# CFS210017030ZZP2005A0.net
KiCad netlist of a schematic drawn in Altium Designer
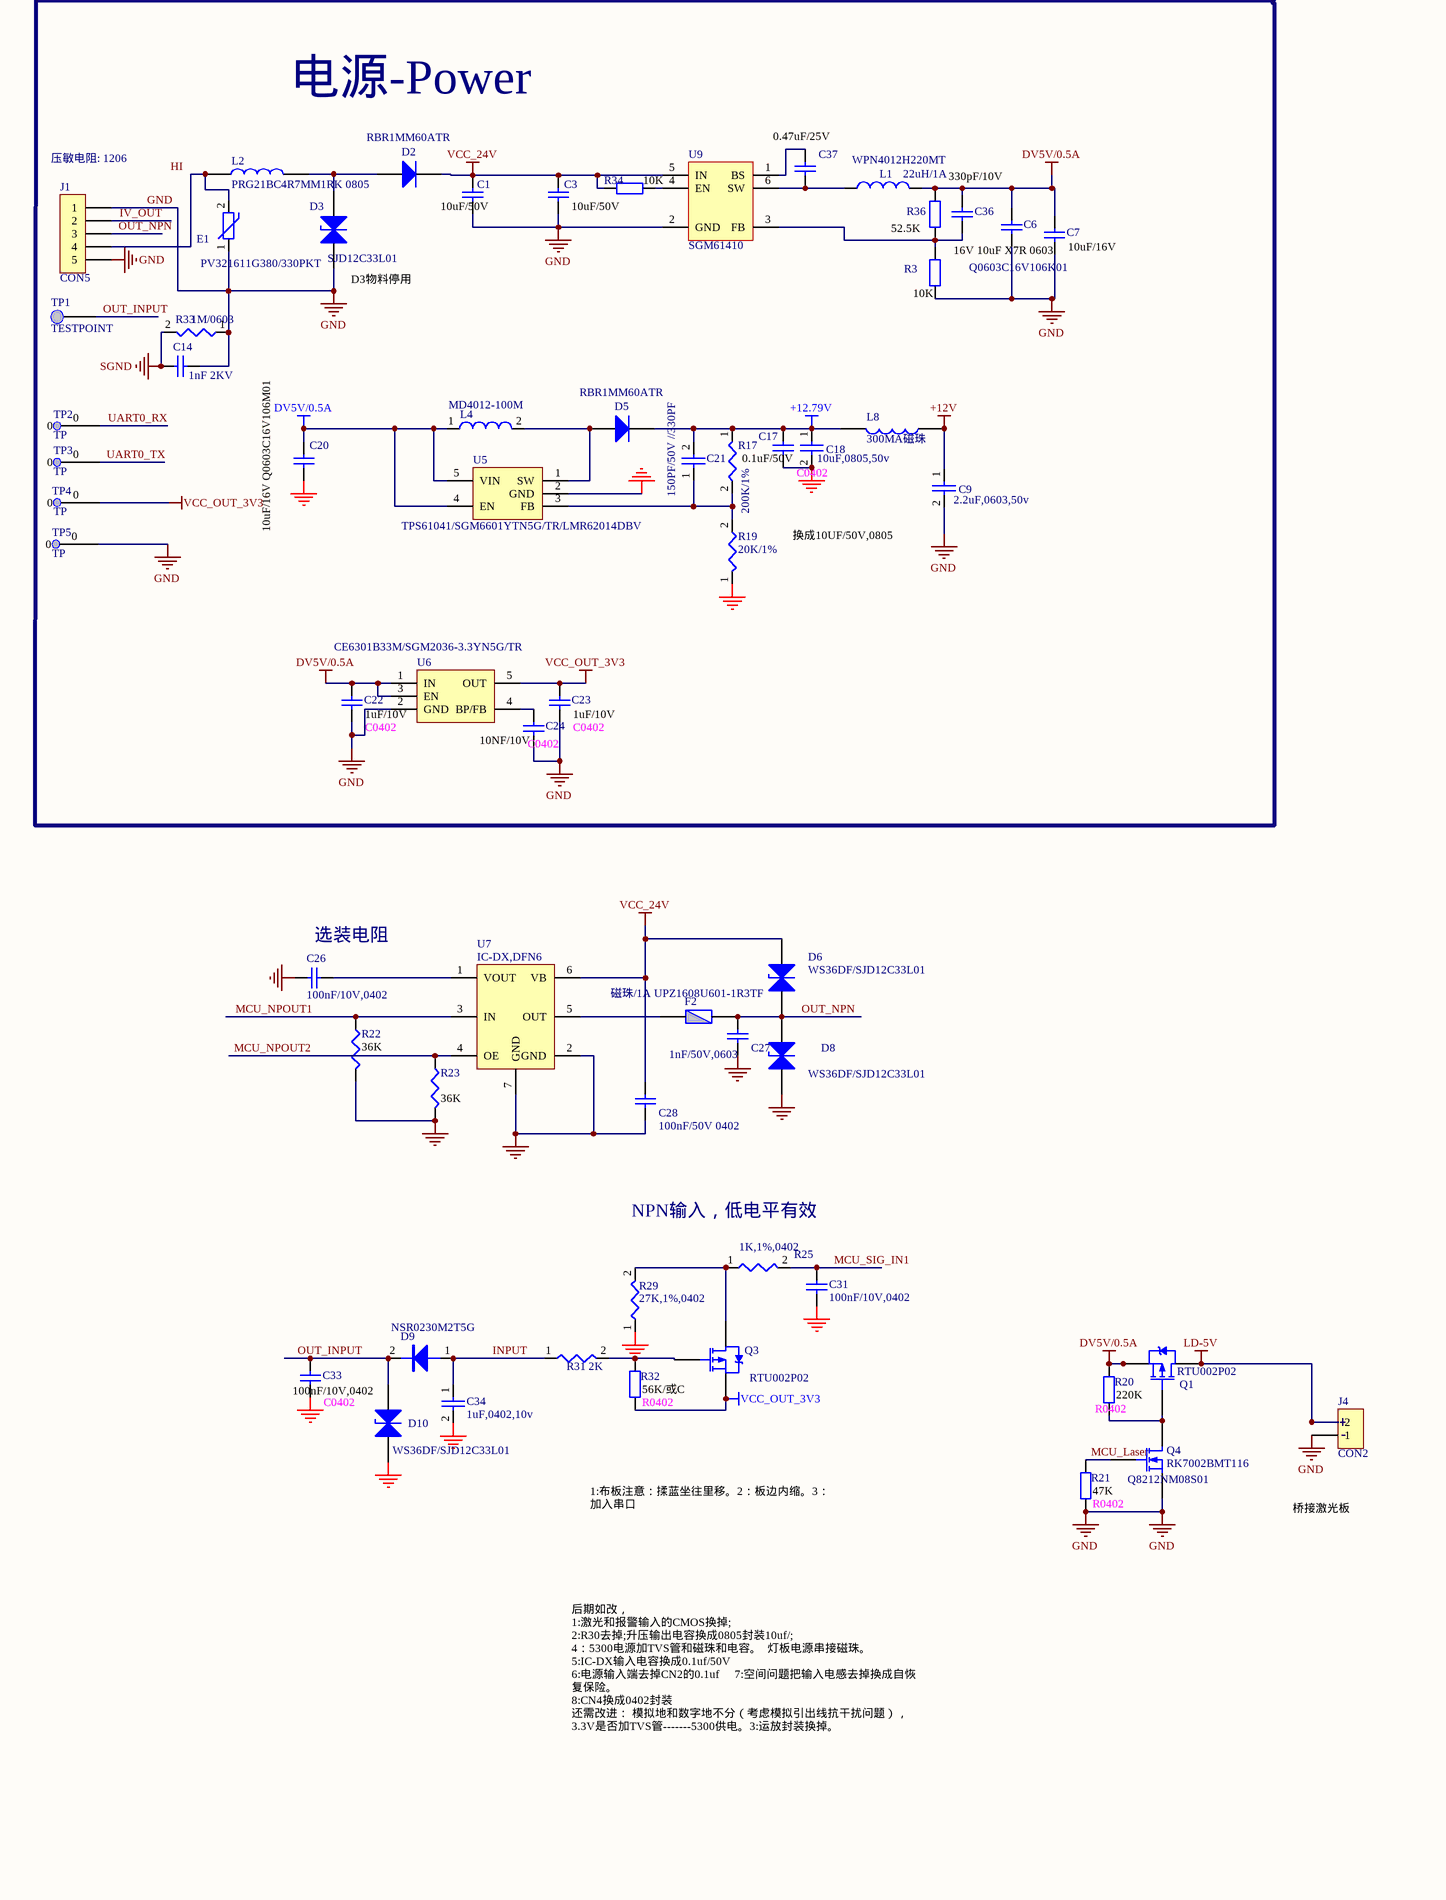
[diagram p0: CFS210017030ZZP2005A0.SchDoc, left]
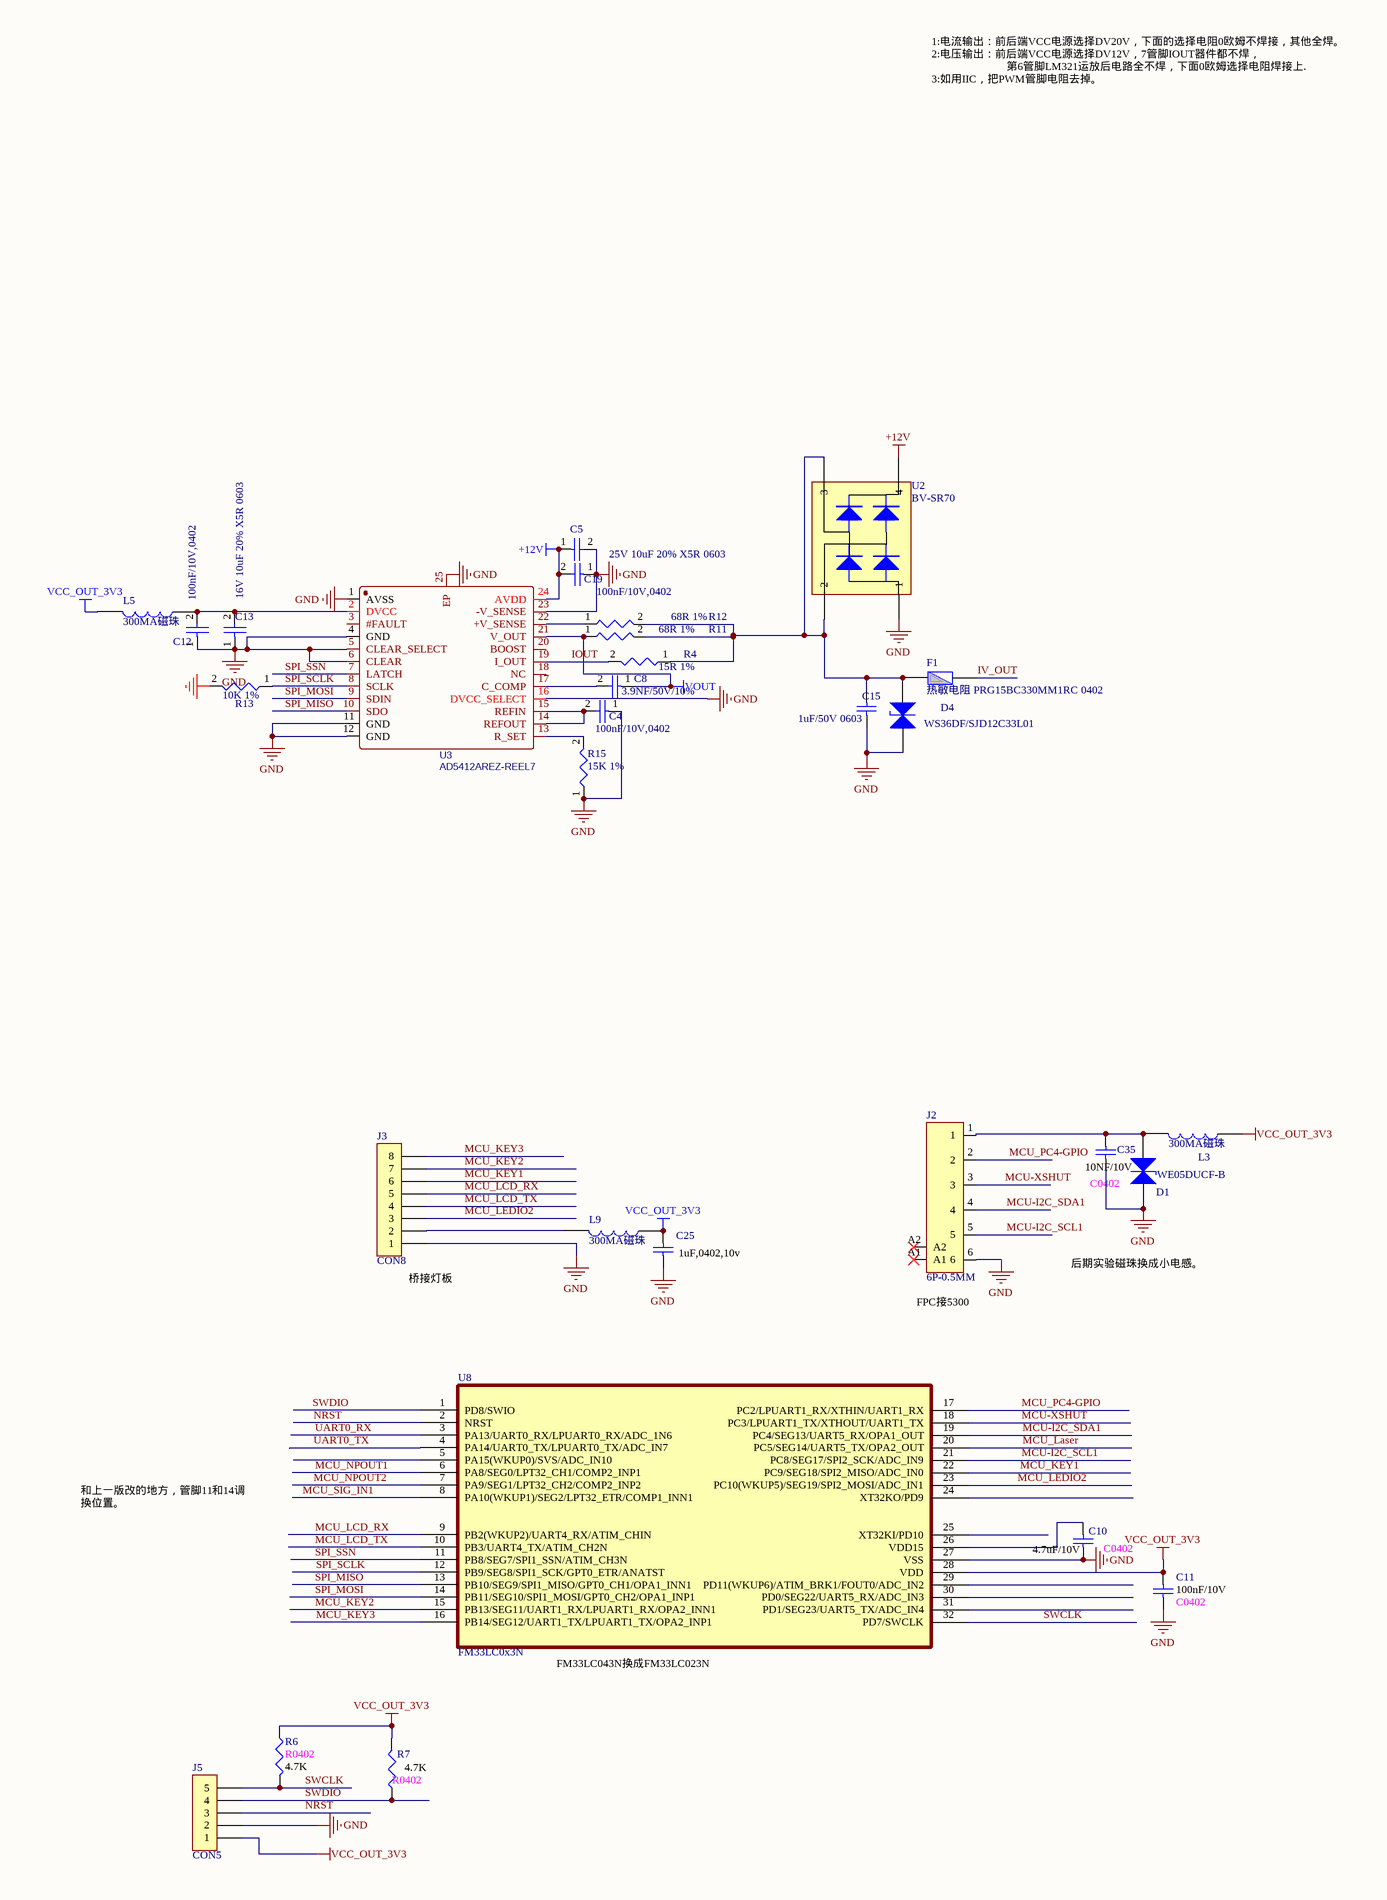
[diagram p1: CFS210017030ZZP2005A0.SchDoc, right]

(export (version "E")
  (design (tool "Eeschema 10.0.6"))
  (components
    (comp (ref "C1")
      (value "10uF/50V")
      (footprint "R0805-Z")
      (description "Capacitor")
      (fields (field (name "Comment") "Q0402C50V223K01") (field (name "PUBLISHER") "Altium Limited"))
      (libsource (lib "Miscellaneous Devices") (part "Cap"))
    )
    (comp (ref "C3")
      (value "10uF/50V")
      (footprint "R0805-Z")
      (description "Capacitor")
      (fields (field (name "Comment") "Q0402C50V223K01") (field (name "PUBLISHER") "Altium Limited"))
      (libsource (lib "Miscellaneous Devices") (part "Cap"))
    )
    (comp (ref "C4")
      (value "100nF/10V,0402")
      (footprint "R0402-Z")
      (description "Capacitor")
      (libsource (lib "*") (part "CAP"))
    )
    (comp (ref "C5")
      (value "25V 10uF 20% X5R 0603")
      (footprint "R0603-Z")
      (description "Capacitor")
      (libsource (lib "*") (part "CAP"))
    )
    (comp (ref "C6")
      (value "Q0603C16V106K01")
      (footprint "R0603-Z")
      (description "Capacitor")
      (fields (field (name "ALTIUM_VALUE") "16V 10uF X7R 0603") (field (name "PUBLISHER") "Altium Limited"))
      (libsource (lib "Miscellaneous Devices") (part "Cap"))
    )
    (comp (ref "C7")
      (value "10uF/16V")
      (footprint "R0603-Z")
      (description "Capacitor")
      (fields (field (name "Comment") "Q0603C16V106K01") (field (name "PUBLISHER") "Altium Limited"))
      (libsource (lib "Miscellaneous Devices") (part "Cap"))
    )
    (comp (ref "C8")
      (value "3.9NF/50V/10%")
      (footprint "R0402-Z")
      (description "Capacitor")
      (libsource (lib "*") (part "CAP"))
    )
    (comp (ref "C9")
      (value "2.2uF,0603,50v")
      (footprint "R0603-Z")
      (description "Capacitor")
      (libsource (lib "*") (part "CAP"))
    )
    (comp (ref "C10")
      (value "4.7uF/10V")
      (footprint "R0402-Z")
      (description "Capacitor (Semiconductor SIM Model)")
      (fields (field (name "PACKAGEREFERENCE") "C0402") (field (name "PUBLISHER") "Altium Limited"))
      (libsource (lib "Miscellaneous Devices") (part "Cap Semi"))
    )
    (comp (ref "C11")
      (value "100nF/10V")
      (footprint "R0402-Z")
      (description "Capacitor (Semiconductor SIM Model)")
      (fields
        (field (name "PACKAGEREFERENCE") "C0402")
        (field (name "Comment") "100nF/10V,0402")
        (field (name "PUBLISHER") "Altium Limited")
      )
      (libsource (lib "Miscellaneous Devices") (part "Cap Semi"))
    )
    (comp (ref "C12")
      (value "100nF/10V,0402")
      (footprint "R0402-Z")
      (description "Capacitor")
      (libsource (lib "*") (part "CAP"))
    )
    (comp (ref "C13")
      (value "16V 10uF 20% X5R 0603")
      (footprint "R0603-Z")
      (description "Capacitor")
      (libsource (lib "*") (part "CAP"))
    )
    (comp (ref "C14")
      (value "1nF 2KV")
      (footprint "CR3216-1206")
      (description "Capacitor")
      (fields (field (name "PUBLISHER") "Altium Limited"))
      (libsource (lib "Miscellaneous Devices") (part "Cap"))
    )
    (comp (ref "C15")
      (value "1uF/50V 0603")
      (footprint "R0603-Z")
      (fields (field (name "PUBLISHER") "Altium Limited"))
      (libsource (lib "Miscellaneous Devices") (part "Cap"))
    )
    (comp (ref "C17")
      (value "0.1uF/50V")
      (footprint "R0402-Z")
      (description "Capacitor")
      (fields
        (field (name "PACKAGEREFERENCE") "C0402")
        (field (name "Comment") "Q0402C50V223K01")
        (field (name "PUBLISHER") "Altium Limited")
      )
      (libsource (lib "Miscellaneous Devices") (part "Cap"))
    )
    (comp (ref "C18")
      (value "10uF,0805,50v")
      (footprint "R0805-Z")
      (description "Capacitor")
      (libsource (lib "*") (part "CAP"))
    )
    (comp (ref "C19")
      (value "100nF/10V,0402")
      (footprint "R0402-Z")
      (description "Capacitor")
      (libsource (lib "*") (part "CAP"))
    )
    (comp (ref "C20")
      (value "10uF/16V Q0603C16V106M01")
      (footprint "R0603-Z")
      (description "Capacitor")
      (fields (field (name "Comment") "Q0603C16V106K01") (field (name "PUBLISHER") "Altium Limited"))
      (libsource (lib "Miscellaneous Devices") (part "Cap"))
    )
    (comp (ref "C21")
      (value "150PF/50V //330PF")
      (footprint "R0402-Z")
      (description "Capacitor")
      (libsource (lib "*") (part "CAP"))
    )
    (comp (ref "C22")
      (value "1uF/10V")
      (footprint "R0402-Z")
      (description "Capacitor")
      (fields
        (field (name "PACKAGEREFERENCE") "C0402")
        (field (name "Comment") "Q0402C50V223K01")
        (field (name "PUBLISHER") "Altium Limited")
      )
      (libsource (lib "Miscellaneous Devices") (part "Cap"))
    )
    (comp (ref "C23")
      (value "1uF/10V")
      (footprint "R0402-Z")
      (description "Capacitor")
      (fields
        (field (name "PACKAGEREFERENCE") "C0402")
        (field (name "Comment") "Q0402C50V223K01")
        (field (name "PUBLISHER") "Altium Limited")
      )
      (libsource (lib "Miscellaneous Devices") (part "Cap"))
    )
    (comp (ref "C24")
      (value "10NF/10V")
      (footprint "R0402-Z")
      (description "Capacitor")
      (fields
        (field (name "PACKAGEREFERENCE") "C0402")
        (field (name "Comment") "Q0402C50V223K01")
        (field (name "PUBLISHER") "Altium Limited")
      )
      (libsource (lib "Miscellaneous Devices") (part "Cap"))
    )
    (comp (ref "C25")
      (value "1uF,0402,10v")
      (footprint "R0402-Z")
      (description "Capacitor (Semiconductor SIM Model)")
      (fields (field (name "PUBLISHER") "Altium Limited"))
      (libsource (lib "Miscellaneous Devices") (part "Cap Semi"))
    )
    (comp (ref "C26")
      (value "100nF/10V,0402")
      (footprint "R0402-Z")
      (description "Capacitor")
      (fields (field (name "PUBLISHER") "Altium Limited"))
      (libsource (lib "*") (part "Cap"))
    )
    (comp (ref "C27")
      (value "1nF/50V,0603")
      (footprint "R0603-Z")
      (description "Capacitor")
      (fields (field (name "PUBLISHER") "Altium Limited"))
      (libsource (lib "*") (part "Cap"))
    )
    (comp (ref "C28")
      (value "100nF/50V 0402")
      (footprint "R0402-Z")
      (description "Capacitor")
      (fields (field (name "PUBLISHER") "Altium Limited"))
      (libsource (lib "*") (part "Cap"))
    )
    (comp (ref "C31")
      (value "100nF/10V,0402")
      (footprint "R0402-Z")
      (description "Capacitor")
      (fields (field (name "PUBLISHER") "Altium Limited"))
      (libsource (lib "*") (part "Cap"))
    )
    (comp (ref "C33")
      (value "100nF/10V,0402")
      (footprint "R0402-Z")
      (description "Capacitor")
      (fields
        (field (name "PACKAGEREFERENCE") "C0402")
        (field (name "Comment") "Q0402C50V223K01")
        (field (name "PUBLISHER") "Altium Limited")
      )
      (libsource (lib "Miscellaneous Devices") (part "Cap"))
    )
    (comp (ref "C34")
      (value "1uF,0402,10v")
      (footprint "R0402-Z")
      (description "Capacitor")
      (libsource (lib "*") (part "CAP"))
    )
    (comp (ref "C35")
      (value "10NF/10V")
      (footprint "R0402-Z")
      (description "Capacitor")
      (fields
        (field (name "PACKAGEREFERENCE") "C0402")
        (field (name "Comment") "Q0402C50V223K01")
        (field (name "PUBLISHER") "Altium Limited")
      )
      (libsource (lib "Miscellaneous Devices") (part "Cap"))
    )
    (comp (ref "C36")
      (value "330pF/10V")
      (footprint "R0402-Z")
      (description "Capacitor")
      (fields (field (name "Comment") "Q0402C50V223K01") (field (name "PUBLISHER") "Altium Limited"))
      (libsource (lib "Miscellaneous Devices") (part "Cap"))
    )
    (comp (ref "C37")
      (value "0.47uF/25V")
      (footprint "R0402-Z")
      (description "Capacitor")
      (fields (field (name "Comment") "Q0402C50V223K01") (field (name "PUBLISHER") "Altium Limited"))
      (libsource (lib "Miscellaneous Devices") (part "Cap"))
    )
    (comp (ref "D1") (value "WE05DUCF-B") (footprint "WS36DF") (libsource (lib "*") (part "PSD36C")))
    (comp (ref "D2")
      (value "RBR1MM60ATR")
      (footprint "SOD-123Z")
      (description "Default Diode")
      (fields (field (name "PUBLISHER") "Altium Limited"))
      (libsource (lib "Miscellaneous Devices") (part "Diode"))
    )
    (comp (ref "D3") (value "SJD12C33L01") (footprint "SOD-123S") (libsource (lib "*") (part "PSD36C")))
    (comp (ref "D4") (value "WS36DF/SJD12C33L01") (footprint "WS36DF") (libsource (lib "*") (part "PSD36C")))
    (comp (ref "D5")
      (value "RBR1MM60ATR")
      (footprint "SOD-123Z")
      (description "Default Diode")
      (fields (field (name "PUBLISHER") "Altium Limited"))
      (libsource (lib "Miscellaneous Devices") (part "Diode"))
    )
    (comp (ref "D6") (value "WS36DF/SJD12C33L01") (footprint "WS36DF") (libsource (lib "*") (part "PSD36C")))
    (comp (ref "D8") (value "WS36DF/SJD12C33L01") (footprint "WS36DF") (libsource (lib "*") (part "PSD36C")))
    (comp (ref "D9")
      (value "NSR0230M2T5G")
      (footprint "SOD723")
      (description "Diode")
      (libsource (lib "*") (part "DIODE"))
    )
    (comp (ref "D10") (value "WS36DF/SJD12C33L01") (footprint "WS36DF") (libsource (lib "*") (part "PSD36C")))
    (comp (ref "E1")
      (value "PV321611G380/330PKT")
      (footprint "FPV3216")
      (description "PV321611G380PKT")
      (fields (field (name "压敏电阻") "1206"))
      (libsource (lib "*") (part "VARISTOR"))
    )
    (comp (ref "F1")
      (value "热敏电阻 PRG15BC330MM1RC 0402")
      (footprint "R0402-Z")
      (description "自恢复保险")
      (libsource (lib "YAANSch20090511") (part "PTC"))
    )
    (comp (ref "F2")
      (value "磁珠/1A UPZ1608U601-1R3TF")
      (footprint "R0603-Z")
      (description "自恢复保险")
      (libsource (lib "YAANSch20090511") (part "PTC"))
    )
    (comp (ref "J1")
      (value "CON5")
      (footprint "CON1.695-5")
      (description "Connector")
      (libsource (lib "YAANSch2021") (part "CON5"))
    )
    (comp (ref "J2") (value "6P-0.5MM") (footprint "FPC-0.5-6") (libsource (lib "*") (part "6PIN_1")))
    (comp (ref "J3")
      (value "CON8")
      (footprint "CON8-QIAOJIE")
      (description "Connector")
      (fields (field (name "MANUFACTURER") "津达电子"))
      (libsource (lib "YAANSch") (part "CON8"))
    )
    (comp (ref "J4")
      (value "CON2")
      (footprint "JIGUANGQIAO")
      (description "Connector")
      (libsource (lib "YAANSch2021") (part "CON2"))
    )
    (comp (ref "J5")
      (value "CON5")
      (footprint "PH1.27-5")
      (description "Connector")
      (fields (field (name "MANUFACTURER") "津达电子"))
      (libsource (lib "YAANSch") (part "CON5"))
    )
    (comp (ref "L1")
      (value "WPN4012H220MT")
      (footprint "WPN4012H220MT")
      (description "Inductor")
      (fields (field (name "ALTIUM_VALUE") "22uH/1A") (field (name "PUBLISHER") "Altium Limited"))
      (libsource (lib "Miscellaneous Devices") (part "Inductor"))
    )
    (comp (ref "L2")
      (value "PRG21BC4R7MM1RK 0805")
      (footprint "R0805-Z")
      (libsource (lib "YAANSch20090511") (part "INDUCTOR1"))
    )
    (comp (ref "L3")
      (value "300MA磁珠")
      (footprint "R0402-Z")
      (libsource (lib "YAANSch20090511") (part "INDUCTOR1"))
    )
    (comp (ref "L4")
      (value "10UH或12UH/1..3A以上")
      (footprint "MD4012-100M")
      (fields (field (name "ALTIUM_UNNAMED_1") "MD4012-100M"))
      (libsource (lib "*") (part "INDUCTOR"))
    )
    (comp (ref "L5")
      (value "300MA磁珠")
      (footprint "R0402-Z")
      (libsource (lib "YAANSch20090511") (part "INDUCTOR1"))
    )
    (comp (ref "L8")
      (value "300MA磁珠")
      (footprint "R0402-Z")
      (libsource (lib "YAANSch20090511") (part "INDUCTOR1"))
    )
    (comp (ref "L9")
      (value "300MA磁珠")
      (footprint "R0402-Z")
      (libsource (lib "YAANSch20090511") (part "INDUCTOR1"))
    )
    (comp (ref "Q1")
      (value "RTU002P02")
      (footprint "SOT-323")
      (description "P-Channel Power MOSFET")
      (fields (field (name "PUBLISHER") "Altium Limited"))
      (libsource (lib "Miscellaneous Devices") (part "PMOS-2"))
    )
    (comp (ref "Q3")
      (value "RTU002P02")
      (footprint "SOT-323")
      (description "P-Channel Power MOSFET")
      (fields (field (name "PUBLISHER") "Altium Limited"))
      (libsource (lib "Miscellaneous Devices") (part "PMOS-2"))
    )
    (comp (ref "Q4")
      (value "RK7002BMT116")
      (footprint "SOT-23")
      (description "N-Channel MOSFET")
      (fields (field (name "ALTIUM_UNNAMED_1") "Q8212NM08S01") (field (name "PUBLISHER") "Altium Limited"))
      (libsource (lib "Miscellaneous Devices") (part "MOSFET-N"))
    )
    (comp (ref "R3")
      (value "10K")
      (footprint "R0402-Z")
      (description "Resistor")
      (fields (field (name "PUBLISHER") "Altium Limited"))
      (libsource (lib "") (part "Res2_1"))
    )
    (comp (ref "R4") (value "15R 1%") (footprint "R0402-Z") (libsource (lib "*") (part "RES1")))
    (comp (ref "R6")
      (value "4.7K")
      (footprint "R0402-Z")
      (description "Resistor")
      (fields (field (name "PACKAGEREFERENCE") "R0402") (field (name "PUBLISHER") "Altium Limited"))
      (libsource (lib "Miscellaneous Devices") (part "Res3"))
    )
    (comp (ref "R7")
      (value "4.7K")
      (footprint "R0402-Z")
      (description "Resistor")
      (fields (field (name "PACKAGEREFERENCE") "R0402") (field (name "PUBLISHER") "Altium Limited"))
      (libsource (lib "Miscellaneous Devices") (part "Res3"))
    )
    (comp (ref "R11") (value "68R 1%") (footprint "R0402-Z") (libsource (lib "*") (part "RES1")))
    (comp (ref "R12") (value "68R 1%") (footprint "R0402-Z") (libsource (lib "*") (part "RES1")))
    (comp (ref "R13") (value "10K 1%") (footprint "R0402-Z") (libsource (lib "*") (part "RES1")))
    (comp (ref "R15") (value "15K 1%") (footprint "R0402-Z") (libsource (lib "*") (part "RES1")))
    (comp (ref "R17") (value "200K/1%") (footprint "R0402-Z") (libsource (lib "*") (part "RES1")))
    (comp (ref "R19") (value "20K/1%") (footprint "R0402-Z") (libsource (lib "*") (part "RES1")))
    (comp (ref "R20")
      (value "220K")
      (footprint "R0402-Z")
      (description "Resistor")
      (fields (field (name "PACKAGEREFERENCE") "R0402") (field (name "PUBLISHER") "Altium Limited"))
      (libsource (lib "") (part "Res2_1"))
    )
    (comp (ref "R21")
      (value "47K")
      (footprint "R0402-Z")
      (description "Resistor")
      (fields (field (name "PACKAGEREFERENCE") "R0402") (field (name "PUBLISHER") "Altium Limited"))
      (libsource (lib "") (part "Res2_1"))
    )
    (comp (ref "R22")
      (value "36K")
      (footprint "R0402-Z")
      (description "Resistor")
      (fields (field (name "PUBLISHER") "Altium Limited"))
      (libsource (lib "Miscellaneous Devices") (part "Res3"))
    )
    (comp (ref "R23")
      (value "36K")
      (footprint "R0402-Z")
      (description "Resistor")
      (fields (field (name "PUBLISHER") "Altium Limited"))
      (libsource (lib "Miscellaneous Devices") (part "Res3"))
    )
    (comp (ref "R25") (value "1K,1%,0402") (footprint "R0402-Z") (libsource (lib "*") (part "RES1")))
    (comp (ref "R29") (value "27K,1%,0402") (footprint "R0402-Z") (libsource (lib "*") (part "RES1")))
    (comp (ref "R31") (value "2K") (footprint "R0402-Z") (libsource (lib "*") (part "RES1")))
    (comp (ref "R32")
      (value "56K/或C")
      (footprint "R0402-Z")
      (description "Resistor")
      (fields
        (field (name "PACKAGEREFERENCE") "R0402")
        (field (name "Comment") "56K")
        (field (name "PUBLISHER") "Altium Limited")
      )
      (libsource (lib "") (part "Res2_1"))
    )
    (comp (ref "R33") (value "1M/0603") (footprint "R0603-Z") (libsource (lib "*") (part "RES1")))
    (comp (ref "R34")
      (value "10K")
      (footprint "R0402-Z")
      (description "Resistor")
      (fields (field (name "PUBLISHER") "Altium Limited"))
      (libsource (lib "Miscellaneous Devices") (part "Res2"))
    )
    (comp (ref "R36")
      (value "52.5K")
      (footprint "R0402-Z")
      (description "Resistor")
      (fields (field (name "PUBLISHER") "Altium Limited"))
      (libsource (lib "") (part "Res2_1"))
    )
    (comp (ref "TP1")
      (value "TESTPOINT")
      (footprint "TP1-1")
      (libsource (lib "YAANSch2021") (part "TESTPOINT"))
    )
    (comp (ref "TP2") (value "TP") (footprint "TP1") (libsource (lib "YAANSch2021") (part "TP")))
    (comp (ref "TP3") (value "TP") (footprint "TP1") (libsource (lib "YAANSch2021") (part "TP")))
    (comp (ref "TP4") (value "TP") (footprint "TP1") (libsource (lib "YAANSch2021") (part "TP")))
    (comp (ref "TP5") (value "TP") (footprint "TP1") (libsource (lib "YAANSch2021") (part "TP")))
    (comp (ref "U2") (value "BV-SR70") (footprint "CD143A") (libsource (lib "OSM40-主控板") (part "CD143A")))
    (comp (ref "U3")
      (value "AD5412AREZ-REEL7")
      (footprint "AD5422")
      (fields (field (name "BOM_SUPPLIER PART") "C27993"))
      (libsource (lib "altium-import") (part "root_0_AD5412AREZ-REEL7_"))
    )
    (comp (ref "U5")
      (value "TPS61041/SGM6601YTN5G/TR/LMR62014DBV")
      (footprint "SOT23-5-LMR62014")
      (libsource (lib "IC芯片") (part "TPS61041"))
    )
    (comp (ref "U6")
      (value "CE6301B33M/SGM2036-3.3YN5G/TR")
      (footprint "SOT23-5")
      (libsource (lib "Schlib1") (part "SGM2036-3.3YN5G/TR"))
    )
    (comp (ref "U7") (value "IC-DX,DFN6") (footprint "IC-DX") (libsource (lib "*") (part "IC-DX")))
    (comp (ref "U8") (value "FM33LC0x3N") (footprint "QFN32") (libsource (lib "FM_MCU") (part "FM33LC0x3N")))
    (comp (ref "U9") (value "SGM61410") (footprint "SOT23-6-Z") (libsource (lib "Schlib1") (part "HM2459B")))
  )
  (nets
    (net (code "1") (name "+12.79V") (class "Default")
      (node (ref "C17") (pin "2") (pinfunction "2_2") (pintype "passive"))
      (node (ref "C18") (pin "1") (pinfunction "1_1") (pintype "passive"))
      (node (ref "C21") (pin "2") (pinfunction "2_2") (pintype "passive"))
      (node (ref "D5") (pin "2") (pinfunction "K_2") (pintype "passive"))
      (node (ref "L8") (pin "2") (pinfunction "2_2") (pintype "passive"))
      (node (ref "R17") (pin "1") (pinfunction "1_1") (pintype "passive"))
    )
    (net (code "2") (name "+12V") (class "Default")
      (node (ref "C19") (pin "2") (pinfunction "2_2") (pintype "passive"))
      (node (ref "C5") (pin "1") (pinfunction "1_1") (pintype "passive"))
      (node (ref "C9") (pin "1") (pinfunction "1_1") (pintype "passive"))
      (node (ref "L8") (pin "1") (pinfunction "1_1") (pintype "passive"))
      (node (ref "U2") (pin "4") (pinfunction "4_4") (pintype "passive"))
      (node (ref "U3") (pin "24") (pinfunction "AVDD_24") (pintype "passive"))
    )
    (net (code "4") (name "/INPUT") (class "Default")
      (node (ref "C34") (pin "1") (pinfunction "1_1") (pintype "passive"))
      (node (ref "D9") (pin "1") (pinfunction "A_1") (pintype "passive"))
      (node (ref "R31") (pin "1") (pinfunction "1_1") (pintype "passive"))
    )
    (net (code "5") (name "/IOUT") (class "Default")
      (node (ref "R4") (pin "2") (pinfunction "2_2") (pintype "passive"))
      (node (ref "U3") (pin "19") (pinfunction "I_OUT_19") (pintype "passive"))
    )
    (net (code "6") (name "/IV_OUT") (class "Default")
      (node (ref "F1") (pin "1") (pinfunction "1_1") (pintype "passive"))
      (node (ref "J1") (pin "2") (pinfunction "2_2") (pintype "passive"))
    )
    (net (code "7") (name "/MCU-I2C_SCL1") (class "Default")
      (node (ref "J2") (pin "5") (pinfunction "5_5") (pintype "passive"))
      (node (ref "U8") (pin "21") (pinfunction "PC8/SEG17/SPI2_SCK/ADC_IN9_21") (pintype "passive"))
    )
    (net (code "8") (name "/MCU-I2C_SDA1") (class "Default")
      (node (ref "J2") (pin "4") (pinfunction "4_4") (pintype "passive"))
      (node (ref "U8") (pin "19") (pinfunction "PC4/SEG13/UART5_RX/OPA1_OUT_19") (pintype "passive"))
    )
    (net (code "9") (name "/MCU-XSHUT") (class "Default")
      (node (ref "J2") (pin "3") (pinfunction "3_3") (pintype "passive"))
      (node (ref "U8") (pin "18") (pinfunction "PC3/LPUART1_TX/XTHOUT/UART1_TX_18") (pintype "passive"))
    )
    (net (code "10") (name "/MCU_KEY1") (class "Default")
      (node (ref "J3") (pin "6") (pinfunction "6_6") (pintype "passive"))
      (node (ref "U8") (pin "22") (pinfunction "PC9/SEG18/SPI2_MISO/ADC_IN0_22") (pintype "passive"))
    )
    (net (code "11") (name "/MCU_KEY2") (class "Default")
      (node (ref "J3") (pin "7") (pinfunction "7_7") (pintype "passive"))
      (node (ref "U8") (pin "15") (pinfunction "PB13/SEG11/UART1_RX/LPUART1_RX/OPA2_INN1_15") (pintype "passive"))
    )
    (net (code "12") (name "/MCU_KEY3") (class "Default")
      (node (ref "J3") (pin "8") (pinfunction "8_8") (pintype "passive"))
      (node (ref "U8") (pin "16") (pinfunction "PB14/SEG12/UART1_TX/LPUART1_TX/OPA2_INP1_16") (pintype "passive"))
    )
    (net (code "13") (name "/MCU_LCD_RX") (class "Default")
      (node (ref "J3") (pin "5") (pinfunction "5_5") (pintype "passive"))
      (node (ref "U8") (pin "9") (pinfunction "PB2(WKUP2)/UART4_RX/ATIM_CHIN_9") (pintype "passive"))
    )
    (net (code "14") (name "/MCU_LCD_TX") (class "Default")
      (node (ref "J3") (pin "4") (pinfunction "4_4") (pintype "passive"))
      (node (ref "U8") (pin "10") (pinfunction "PB3/UART4_TX/ATIM_CH2N_10") (pintype "passive"))
    )
    (net (code "15") (name "/MCU_LEDIO2") (class "Default")
      (node (ref "J3") (pin "3") (pinfunction "3_3") (pintype "passive"))
      (node (ref "U8") (pin "23") (pinfunction "PC10(WKUP5)/SEG19/SPI2_MOSI/ADC_IN1_23") (pintype "passive"))
    )
    (net (code "16") (name "/MCU_Laser") (class "Default")
      (node (ref "Q4") (pin "2") (pinfunction "G_2") (pintype "passive"))
      (node (ref "R21") (pin "2") (pinfunction "2_2") (pintype "passive"))
      (node (ref "U8") (pin "20") (pinfunction "PC5/SEG14/UART5_TX/OPA2_OUT_20") (pintype "passive"))
    )
    (net (code "17") (name "/MCU_NPOUT1") (class "Default")
      (node (ref "R22") (pin "1") (pinfunction "1_1") (pintype "passive"))
      (node (ref "U7") (pin "3") (pinfunction "IN_3") (pintype "passive"))
      (node (ref "U8") (pin "6") (pinfunction "PA8/SEG0/LPT32_CH1/COMP2_INP1_6") (pintype "passive"))
    )
    (net (code "18") (name "/MCU_NPOUT2") (class "Default")
      (node (ref "R23") (pin "1") (pinfunction "1_1") (pintype "passive"))
      (node (ref "U7") (pin "4") (pinfunction "OE_4") (pintype "passive"))
      (node (ref "U8") (pin "7") (pinfunction "PA9/SEG1/LPT32_CH2/COMP2_INP2_7") (pintype "passive"))
    )
    (net (code "19") (name "/MCU_PC4-GPIO") (class "Default")
      (node (ref "J2") (pin "2") (pinfunction "2_2") (pintype "passive"))
      (node (ref "U8") (pin "17") (pinfunction "PC2/LPUART1_RX/XTHIN/UART1_RX_17") (pintype "passive"))
    )
    (net (code "20") (name "/MCU_SIG_IN1") (class "Default")
      (node (ref "C31") (pin "2") (pinfunction "2_2") (pintype "passive"))
      (node (ref "R25") (pin "2") (pinfunction "2_2") (pintype "passive"))
      (node (ref "U8") (pin "8") (pinfunction "PA10(WKUP1)/SEG2/LPT32_ETR/COMP1_INN1_8") (pintype "passive"))
    )
    (net (code "21") (name "/NRST") (class "Default")
      (node (ref "J5") (pin "3") (pinfunction "3_3") (pintype "passive"))
      (node (ref "U8") (pin "2") (pinfunction "NRST_2") (pintype "passive"))
    )
    (net (code "22") (name "/OUT_INPUT") (class "Default")
      (node (ref "C33") (pin "2") (pinfunction "2_2") (pintype "passive"))
      (node (ref "D10") (pin "1") (pinfunction "A_1") (pintype "passive"))
      (node (ref "D9") (pin "2") (pinfunction "K_2") (pintype "passive"))
      (node (ref "TP1") (pin "1") (pinfunction "1_1") (pintype "passive"))
    )
    (net (code "23") (name "/OUT_NPN") (class "Default")
      (node (ref "C27") (pin "2") (pinfunction "2_2") (pintype "passive"))
      (node (ref "D6") (pin "2") (pinfunction "K_2") (pintype "passive"))
      (node (ref "D8") (pin "1") (pinfunction "A_1") (pintype "passive"))
      (node (ref "F2") (pin "1") (pinfunction "1_1") (pintype "passive"))
      (node (ref "J1") (pin "3") (pinfunction "3_3") (pintype "passive"))
    )
    (net (code "24") (name "/SPI_MISO") (class "Default")
      (node (ref "U3") (pin "10") (pinfunction "SDO_10") (pintype "passive"))
      (node (ref "U8") (pin "13") (pinfunction "PB10/SEG9/SPI1_MISO/GPT0_CH1/OPA1_INN1_13") (pintype "passive"))
    )
    (net (code "25") (name "/SPI_MOSI") (class "Default")
      (node (ref "U3") (pin "9") (pinfunction "SDIN_9") (pintype "passive"))
      (node (ref "U8") (pin "14") (pinfunction "PB11/SEG10/SPI1_MOSI/GPT0_CH2/OPA1_INP1_14") (pintype "passive"))
    )
    (net (code "26") (name "/SPI_SCLK") (class "Default")
      (node (ref "R13") (pin "1") (pinfunction "1_1") (pintype "passive"))
      (node (ref "U3") (pin "8") (pinfunction "SCLK_8") (pintype "passive"))
      (node (ref "U8") (pin "12") (pinfunction "PB9/SEG8/SPI1_SCK/GPT0_ETR/ANATST_12") (pintype "passive"))
    )
    (net (code "27") (name "/SPI_SSN") (class "Default")
      (node (ref "U3") (pin "7") (pinfunction "LATCH_7") (pintype "passive"))
      (node (ref "U8") (pin "11") (pinfunction "PB8/SEG7/SPI1_SSN/ATIM_CH3N_11") (pintype "passive"))
    )
    (net (code "28") (name "/SWCLK") (class "Default")
      (node (ref "J5") (pin "5") (pinfunction "5_5") (pintype "passive"))
      (node (ref "R6") (pin "2") (pinfunction "2_2") (pintype "passive"))
      (node (ref "U8") (pin "32") (pinfunction "PD7/SWCLK_32") (pintype "passive"))
    )
    (net (code "29") (name "/SWDIO") (class "Default")
      (node (ref "J5") (pin "4") (pinfunction "4_4") (pintype "passive"))
      (node (ref "R7") (pin "1") (pinfunction "1_1") (pintype "passive"))
      (node (ref "U8") (pin "1") (pinfunction "PD8/SWIO_1") (pintype "passive"))
    )
    (net (code "30") (name "/UART0_RX") (class "Default")
      (node (ref "TP2") (pin "0") (pinfunction "0_0") (pintype "passive"))
      (node (ref "U8") (pin "3") (pinfunction "PA13/UART0_RX/LPUART0_RX/ADC_1N6_3") (pintype "passive"))
    )
    (net (code "31") (name "/UART0_TX") (class "Default")
      (node (ref "TP3") (pin "0") (pinfunction "0_0") (pintype "passive"))
      (node (ref "U8") (pin "4") (pinfunction "PA14/UART0_TX/LPUART0_TX/ADC_IN7_4") (pintype "passive"))
    )
    (net (code "32") (name "DV5V{slash}0.5A") (class "Default")
      (node (ref "C20") (pin "2") (pinfunction "2_2") (pintype "passive"))
      (node (ref "C22") (pin "2") (pinfunction "2_2") (pintype "passive"))
      (node (ref "C36") (pin "2") (pinfunction "2_2") (pintype "passive"))
      (node (ref "C6") (pin "2") (pinfunction "2_2") (pintype "passive"))
      (node (ref "C7") (pin "2") (pinfunction "2_2") (pintype "passive"))
      (node (ref "L1") (pin "2") (pinfunction "2_2") (pintype "passive"))
      (node (ref "L4") (pin "1") (pinfunction "1_1") (pintype "passive"))
      (node (ref "Q1") (pin "2") (pinfunction "S_2") (pintype "passive"))
      (node (ref "R20") (pin "2") (pinfunction "2_2") (pintype "passive"))
      (node (ref "R36") (pin "2") (pinfunction "2_2") (pintype "passive"))
      (node (ref "U5") (pin "4") (pinfunction "EN_4") (pintype "passive"))
      (node (ref "U5") (pin "5") (pinfunction "VIN_5") (pintype "passive"))
      (node (ref "U6") (pin "1") (pinfunction "IN_1") (pintype "passive"))
      (node (ref "U6") (pin "3") (pinfunction "EN_3") (pintype "passive"))
    )
    (net (code "33") (name "GND") (class "Default")
      (node (ref "C1") (pin "1") (pinfunction "1_1") (pintype "passive"))
      (node (ref "C10") (pin "1") (pinfunction "1_1") (pintype "passive"))
      (node (ref "C11") (pin "1") (pinfunction "1_1") (pintype "passive"))
      (node (ref "C12") (pin "1") (pinfunction "1_1") (pintype "passive"))
      (node (ref "C13") (pin "1") (pinfunction "1_1") (pintype "passive"))
      (node (ref "C14") (pin "1") (pinfunction "1_1") (pintype "passive"))
      (node (ref "C15") (pin "2") (pinfunction "2_2") (pintype "passive"))
      (node (ref "C17") (pin "1") (pinfunction "1_1") (pintype "passive"))
      (node (ref "C18") (pin "2") (pinfunction "2_2") (pintype "passive"))
      (node (ref "C19") (pin "1") (pinfunction "1_1") (pintype "passive"))
      (node (ref "C20") (pin "1") (pinfunction "1_1") (pintype "passive"))
      (node (ref "C22") (pin "1") (pinfunction "1_1") (pintype "passive"))
      (node (ref "C23") (pin "1") (pinfunction "1_1") (pintype "passive"))
      (node (ref "C24") (pin "1") (pinfunction "1_1") (pintype "passive"))
      (node (ref "C25") (pin "1") (pinfunction "1_1") (pintype "passive"))
      (node (ref "C26") (pin "1") (pinfunction "1_1") (pintype "passive"))
      (node (ref "C27") (pin "1") (pinfunction "1_1") (pintype "passive"))
      (node (ref "C28") (pin "1") (pinfunction "1_1") (pintype "passive"))
      (node (ref "C3") (pin "1") (pinfunction "1_1") (pintype "passive"))
      (node (ref "C31") (pin "1") (pinfunction "1_1") (pintype "passive"))
      (node (ref "C33") (pin "1") (pinfunction "1_1") (pintype "passive"))
      (node (ref "C34") (pin "2") (pinfunction "2_2") (pintype "passive"))
      (node (ref "C35") (pin "1") (pinfunction "1_1") (pintype "passive"))
      (node (ref "C4") (pin "1") (pinfunction "1_1") (pintype "passive"))
      (node (ref "C5") (pin "2") (pinfunction "2_2") (pintype "passive"))
      (node (ref "C6") (pin "1") (pinfunction "1_1") (pintype "passive"))
      (node (ref "C7") (pin "1") (pinfunction "1_1") (pintype "passive"))
      (node (ref "C9") (pin "2") (pinfunction "2_2") (pintype "passive"))
      (node (ref "D1") (pin "1") (pinfunction "A_1") (pintype "passive"))
      (node (ref "D10") (pin "2") (pinfunction "K_2") (pintype "passive"))
      (node (ref "D3") (pin "2") (pinfunction "K_2") (pintype "passive"))
      (node (ref "D4") (pin "2") (pinfunction "K_2") (pintype "passive"))
      (node (ref "D8") (pin "2") (pinfunction "K_2") (pintype "passive"))
      (node (ref "E1") (pin "1") (pinfunction "1_1") (pintype "passive"))
      (node (ref "J1") (pin "1") (pinfunction "1_1") (pintype "passive"))
      (node (ref "J1") (pin "5") (pinfunction "5_5") (pintype "passive"))
      (node (ref "J2") (pin "6") (pinfunction "6_6") (pintype "passive"))
      (node (ref "J3") (pin "1") (pinfunction "1_1") (pintype "passive"))
      (node (ref "J4") (pin "1") (pinfunction "1_1") (pintype "passive"))
      (node (ref "J5") (pin "2") (pinfunction "2_2") (pintype "passive"))
      (node (ref "Q4") (pin "3") (pinfunction "S_3") (pintype "passive"))
      (node (ref "R13") (pin "2") (pinfunction "2_2") (pintype "passive"))
      (node (ref "R15") (pin "1") (pinfunction "1_1") (pintype "passive"))
      (node (ref "R19") (pin "1") (pinfunction "1_1") (pintype "passive"))
      (node (ref "R21") (pin "1") (pinfunction "1_1") (pintype "passive"))
      (node (ref "R22") (pin "2") (pinfunction "2_2") (pintype "passive"))
      (node (ref "R23") (pin "2") (pinfunction "2_2") (pintype "passive"))
      (node (ref "R29") (pin "1") (pinfunction "1_1") (pintype "passive"))
      (node (ref "R3") (pin "1") (pinfunction "1_1") (pintype "passive"))
      (node (ref "R33") (pin "1") (pinfunction "1_1") (pintype "passive"))
      (node (ref "TP5") (pin "0") (pinfunction "0_0") (pintype "passive"))
      (node (ref "U2") (pin "1") (pinfunction "1_1") (pintype "passive"))
      (node (ref "U3") (pin "1") (pinfunction "AVSS_1") (pintype "passive"))
      (node (ref "U3") (pin "11") (pinfunction "GND_11") (pintype "passive"))
      (node (ref "U3") (pin "12") (pinfunction "GND_12") (pintype "passive"))
      (node (ref "U3") (pin "16") (pinfunction "DVCC_SELECT_16") (pintype "passive"))
      (node (ref "U3") (pin "23") (pinfunction "-V_SENSE_23") (pintype "passive"))
      (node (ref "U3") (pin "25") (pinfunction "EP_25") (pintype "passive"))
      (node (ref "U3") (pin "4") (pinfunction "GND_4") (pintype "passive"))
      (node (ref "U3") (pin "5") (pinfunction "CLEAR_SELECT_5") (pintype "passive"))
      (node (ref "U3") (pin "6") (pinfunction "CLEAR_6") (pintype "passive"))
      (node (ref "U5") (pin "2") (pinfunction "GND_2") (pintype "passive"))
      (node (ref "U6") (pin "2") (pinfunction "GND_2") (pintype "passive"))
      (node (ref "U7") (pin "2") (pinfunction "GND_2") (pintype "passive"))
      (node (ref "U7") (pin "7") (pinfunction "GND_7") (pintype "passive"))
      (node (ref "U8") (pin "27") (pinfunction "VSS_27") (pintype "passive"))
      (node (ref "U9") (pin "2") (pinfunction "GND_2") (pintype "passive"))
    )
    (net (code "34") (name "LD-5V") (class "Default")
      (node (ref "J4") (pin "2") (pinfunction "2_2") (pintype "passive"))
      (node (ref "Q1") (pin "3") (pinfunction "D_3") (pintype "passive"))
    )
    (net (code "35") (name "Net-(D1-K)") (class "Default")
      (node (ref "C35") (pin "2") (pinfunction "2_2") (pintype "passive"))
      (node (ref "D1") (pin "2") (pinfunction "K_2") (pintype "passive"))
      (node (ref "J2") (pin "1") (pinfunction "1_1") (pintype "passive"))
      (node (ref "L3") (pin "2") (pinfunction "2_2") (pintype "passive"))
    )
    (net (code "36") (name "Net-(D2-A)") (class "Default")
      (node (ref "D2") (pin "1") (pinfunction "A_1") (pintype "passive"))
      (node (ref "D3") (pin "1") (pinfunction "A_1") (pintype "passive"))
      (node (ref "L2") (pin "2") (pinfunction "2_2") (pintype "passive"))
    )
    (net (code "37") (name "Net-(D4-A)") (class "Default")
      (node (ref "C15") (pin "1") (pinfunction "1_1") (pintype "passive"))
      (node (ref "D4") (pin "1") (pinfunction "A_1") (pintype "passive"))
      (node (ref "F1") (pin "2") (pinfunction "2_2") (pintype "passive"))
      (node (ref "R11") (pin "2") (pinfunction "2_2") (pintype "passive"))
      (node (ref "R12") (pin "2") (pinfunction "2_2") (pintype "passive"))
      (node (ref "R4") (pin "1") (pinfunction "1_1") (pintype "passive"))
      (node (ref "U2") (pin "2") (pinfunction "2_2") (pintype "passive"))
      (node (ref "U2") (pin "3") (pinfunction "3_3") (pintype "passive"))
    )
    (net (code "38") (name "Net-(D5-A)") (class "Default")
      (node (ref "D5") (pin "1") (pinfunction "A_1") (pintype "passive"))
      (node (ref "L4") (pin "2") (pinfunction "2_2") (pintype "passive"))
      (node (ref "U5") (pin "1") (pinfunction "SW_1") (pintype "passive"))
    )
    (net (code "39") (name "Net-(E1-Pad2)") (class "Default")
      (node (ref "E1") (pin "2") (pinfunction "2_2") (pintype "passive"))
      (node (ref "J1") (pin "4") (pinfunction "4_4") (pintype "passive"))
      (node (ref "L2") (pin "1") (pinfunction "1_1") (pintype "passive"))
    )
    (net (code "40") (name "Net-(J3-Pad2)") (class "Default")
      (node (ref "J3") (pin "2") (pinfunction "2_2") (pintype "passive"))
      (node (ref "L9") (pin "2") (pinfunction "2_2") (pintype "passive"))
    )
    (net (code "41") (name "Net-(Q1-G)") (class "Default")
      (node (ref "Q1") (pin "1") (pinfunction "G_1") (pintype "passive"))
      (node (ref "Q4") (pin "1") (pinfunction "D_1") (pintype "passive"))
      (node (ref "R20") (pin "1") (pinfunction "1_1") (pintype "passive"))
    )
    (net (code "42") (name "Net-(Q3-D)") (class "Default")
      (node (ref "Q3") (pin "3") (pinfunction "D_3") (pintype "passive"))
      (node (ref "R25") (pin "1") (pinfunction "1_1") (pintype "passive"))
      (node (ref "R29") (pin "2") (pinfunction "2_2") (pintype "passive"))
    )
    (net (code "43") (name "Net-(Q3-G)") (class "Default")
      (node (ref "Q3") (pin "1") (pinfunction "G_1") (pintype "passive"))
      (node (ref "R31") (pin "2") (pinfunction "2_2") (pintype "passive"))
      (node (ref "R32") (pin "2") (pinfunction "2_2") (pintype "passive"))
    )
    (net (code "44") (name "Net-(U3-+V_SENSE)") (class "Default")
      (node (ref "R12") (pin "1") (pinfunction "1_1") (pintype "passive"))
      (node (ref "U3") (pin "22") (pinfunction "+V_SENSE_22") (pintype "passive"))
    )
    (net (code "45") (name "Net-(U3-C_COMP)") (class "Default")
      (node (ref "C8") (pin "2") (pinfunction "2_2") (pintype "passive"))
      (node (ref "U3") (pin "17") (pinfunction "C_COMP_17") (pintype "passive"))
    )
    (net (code "46") (name "Net-(U3-DVCC)") (class "Default")
      (node (ref "C12") (pin "2") (pinfunction "2_2") (pintype "passive"))
      (node (ref "C13") (pin "2") (pinfunction "2_2") (pintype "passive"))
      (node (ref "L5") (pin "1") (pinfunction "1_1") (pintype "passive"))
      (node (ref "U3") (pin "2") (pinfunction "DVCC_2") (pintype "passive"))
    )
    (net (code "47") (name "Net-(U3-REFIN)") (class "Default")
      (node (ref "C4") (pin "2") (pinfunction "2_2") (pintype "passive"))
      (node (ref "U3") (pin "14") (pinfunction "REFOUT_14") (pintype "passive"))
      (node (ref "U3") (pin "15") (pinfunction "REFIN_15") (pintype "passive"))
    )
    (net (code "48") (name "Net-(U3-R_SET)") (class "Default")
      (node (ref "R15") (pin "2") (pinfunction "2_2") (pintype "passive"))
      (node (ref "U3") (pin "13") (pinfunction "R_SET_13") (pintype "passive"))
    )
    (net (code "49") (name "Net-(U5-FB)") (class "Default")
      (node (ref "C21") (pin "1") (pinfunction "1_1") (pintype "passive"))
      (node (ref "R17") (pin "2") (pinfunction "2_2") (pintype "passive"))
      (node (ref "R19") (pin "2") (pinfunction "2_2") (pintype "passive"))
      (node (ref "U5") (pin "3") (pinfunction "FB_3") (pintype "passive"))
    )
    (net (code "50") (name "Net-(U6-BP{slash}FB)") (class "Default")
      (node (ref "C24") (pin "2") (pinfunction "2_2") (pintype "passive"))
      (node (ref "U6") (pin "4") (pinfunction "BP/FB_4") (pintype "passive"))
    )
    (net (code "51") (name "Net-(U7-OUT)") (class "Default")
      (node (ref "F2") (pin "2") (pinfunction "2_2") (pintype "passive"))
      (node (ref "U7") (pin "5") (pinfunction "OUT_5") (pintype "passive"))
    )
    (net (code "52") (name "Net-(U7-VOUT)") (class "Default")
      (node (ref "C26") (pin "2") (pinfunction "2_2") (pintype "passive"))
      (node (ref "U7") (pin "1") (pinfunction "VOUT_1") (pintype "passive"))
    )
    (net (code "53") (name "Net-(U8-VDD15)") (class "Default")
      (node (ref "C10") (pin "2") (pinfunction "2_2") (pintype "passive"))
      (node (ref "U8") (pin "26") (pinfunction "VDD15_26") (pintype "passive"))
    )
    (net (code "54") (name "Net-(U9-BS)") (class "Default")
      (node (ref "C37") (pin "1") (pinfunction "1_1") (pintype "passive"))
      (node (ref "U9") (pin "1") (pinfunction "BS_1") (pintype "passive"))
    )
    (net (code "55") (name "Net-(U9-EN)") (class "Default")
      (node (ref "R34") (pin "1") (pinfunction "1_1") (pintype "passive"))
      (node (ref "U9") (pin "4") (pinfunction "EN_4") (pintype "passive"))
    )
    (net (code "56") (name "Net-(U9-FB)") (class "Default")
      (node (ref "C36") (pin "1") (pinfunction "1_1") (pintype "passive"))
      (node (ref "R3") (pin "2") (pinfunction "2_2") (pintype "passive"))
      (node (ref "R36") (pin "1") (pinfunction "1_1") (pintype "passive"))
      (node (ref "U9") (pin "3") (pinfunction "FB_3") (pintype "passive"))
    )
    (net (code "57") (name "Net-(U9-SW)") (class "Default")
      (node (ref "C37") (pin "2") (pinfunction "2_2") (pintype "passive"))
      (node (ref "L1") (pin "1") (pinfunction "1_1") (pintype "passive"))
      (node (ref "U9") (pin "6") (pinfunction "SW_6") (pintype "passive"))
    )
    (net (code "58") (name "SGND") (class "Default")
      (node (ref "C14") (pin "2") (pinfunction "2_2") (pintype "passive"))
      (node (ref "R33") (pin "2") (pinfunction "2_2") (pintype "passive"))
    )
    (net (code "59") (name "VCC_24V") (class "Default")
      (node (ref "C1") (pin "2") (pinfunction "2_2") (pintype "passive"))
      (node (ref "C28") (pin "2") (pinfunction "2_2") (pintype "passive"))
      (node (ref "C3") (pin "2") (pinfunction "2_2") (pintype "passive"))
      (node (ref "D2") (pin "2") (pinfunction "K_2") (pintype "passive"))
      (node (ref "D6") (pin "1") (pinfunction "A_1") (pintype "passive"))
      (node (ref "R34") (pin "2") (pinfunction "2_2") (pintype "passive"))
      (node (ref "U7") (pin "6") (pinfunction "VB_6") (pintype "passive"))
      (node (ref "U9") (pin "5") (pinfunction "IN_5") (pintype "passive"))
    )
    (net (code "60") (name "VCC_OUT_3V3") (class "Default")
      (node (ref "C11") (pin "2") (pinfunction "2_2") (pintype "passive"))
      (node (ref "C23") (pin "2") (pinfunction "2_2") (pintype "passive"))
      (node (ref "C25") (pin "2") (pinfunction "2_2") (pintype "passive"))
      (node (ref "J5") (pin "1") (pinfunction "1_1") (pintype "passive"))
      (node (ref "L3") (pin "1") (pinfunction "1_1") (pintype "passive"))
      (node (ref "L5") (pin "2") (pinfunction "2_2") (pintype "passive"))
      (node (ref "L9") (pin "1") (pinfunction "1_1") (pintype "passive"))
      (node (ref "Q3") (pin "2") (pinfunction "S_2") (pintype "passive"))
      (node (ref "R32") (pin "1") (pinfunction "1_1") (pintype "passive"))
      (node (ref "R6") (pin "1") (pinfunction "1_1") (pintype "passive"))
      (node (ref "R7") (pin "2") (pinfunction "2_2") (pintype "passive"))
      (node (ref "TP4") (pin "0") (pinfunction "0_0") (pintype "passive"))
      (node (ref "U6") (pin "5") (pinfunction "OUT_5") (pintype "passive"))
      (node (ref "U8") (pin "28") (pinfunction "VDD_28") (pintype "passive"))
    )
    (net (code "61") (name "VOUT") (class "Default")
      (node (ref "C8") (pin "1") (pinfunction "1_1") (pintype "passive"))
      (node (ref "R11") (pin "1") (pinfunction "1_1") (pintype "passive"))
      (node (ref "U3") (pin "21") (pinfunction "V_OUT_21") (pintype "passive"))
    )
    (net (code "62") (name "unconnected-(J2-PadA1)") (class "Default")
      (node (ref "J2") (pin "A1") (pinfunction "A1_A1") (pintype "passive+no_connect"))
    )
    (net (code "63") (name "unconnected-(J2-PadA2)") (class "Default")
      (node (ref "J2") (pin "A2") (pinfunction "A2_A2") (pintype "passive+no_connect"))
    )
    (net (code "64") (name "unconnected-(U3-#FAULT-Pad3)") (class "Default")
      (node (ref "U3") (pin "3") (pinfunction "#FAULT_3") (pintype "passive"))
    )
    (net (code "65") (name "unconnected-(U3-BOOST-Pad20)") (class "Default")
      (node (ref "U3") (pin "20") (pinfunction "BOOST_20") (pintype "passive"))
    )
    (net (code "66") (name "unconnected-(U3-NC-Pad18)") (class "Default")
      (node (ref "U3") (pin "18") (pinfunction "NC_18") (pintype "passive"))
    )
    (net (code "67") (name "unconnected-(U8-PA15(WKUP0){slash}SVS{slash}ADC_IN10-Pad5)") (class "Default")
      (node (ref "U8") (pin "5") (pinfunction "PA15(WKUP0)/SVS/ADC_IN10_5") (pintype "passive"))
    )
    (net (code "68") (name "unconnected-(U8-PD0{slash}SEG22{slash}UART5_RX{slash}ADC_IN3-Pad30)") (class "Default")
      (node (ref "U8") (pin "30") (pinfunction "PD0/SEG22/UART5_RX/ADC_IN3_30") (pintype "passive"))
    )
    (net (code "69") (name "unconnected-(U8-PD1{slash}SEG23{slash}UART5_TX{slash}ADC_IN4-Pad31)") (class "Default")
      (node (ref "U8") (pin "31") (pinfunction "PD1/SEG23/UART5_TX/ADC_IN4_31") (pintype "passive"))
    )
    (net (code "70") (name "unconnected-(U8-PD11(WKUP6){slash}ATIM_BRK1{slash}FOUT0{slash}ADC_IN2-Pad29)") (class "Default")
      (node (ref "U8") (pin "29") (pinfunction "PD11(WKUP6)/ATIM_BRK1/FOUT0/ADC_IN2_29") (pintype "passive"))
    )
    (net (code "71") (name "unconnected-(U8-XT32KI{slash}PD10-Pad25)") (class "Default")
      (node (ref "U8") (pin "25") (pinfunction "XT32KI/PD10_25") (pintype "passive"))
    )
    (net (code "72") (name "unconnected-(U8-XT32KO{slash}PD9-Pad24)") (class "Default")
      (node (ref "U8") (pin "24") (pinfunction "XT32KO/PD9_24") (pintype "passive"))
    )
  )
)
